# untitled2b.net
KiCad netlist of a schematic drawn in EAGLE
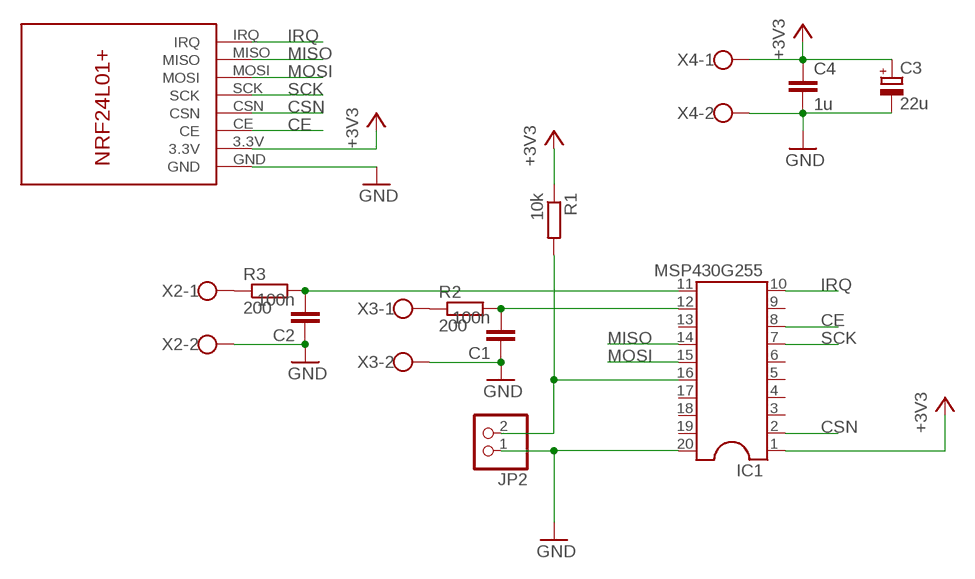
[diagram p0: schematic, sheet 1]

(export (version "E")
  (design (tool "Eeschema 10.0.6"))
  (components
    (comp (ref "C1")
      (value "100n")
      (footprint "eagle-import:C050-025X075")
      (libsource (lib "eagle-import") (part "C-EU050-025X075"))
    )
    (comp (ref "C2")
      (value "100n")
      (footprint "eagle-import:C050-025X075")
      (libsource (lib "eagle-import") (part "C-EU050-025X075"))
    )
    (comp (ref "C3")
      (value "22u")
      (footprint "eagle-import:E5-8,5")
      (libsource (lib "eagle-import") (part "CPOL-EUE5-8.5"))
    )
    (comp (ref "C4")
      (value "1u")
      (footprint "eagle-import:C050-045X075")
      (libsource (lib "eagle-import") (part "C-EU050-045X075"))
    )
    (comp (ref "IC1")
      (value "MSP430G255")
      (footprint "eagle-import:SOCKET-20")
      (libsource (lib "eagle-import") (part "DIL20S"))
    )
    (comp (ref "JP2")
      (value "PINHD-1X2")
      (footprint "eagle-import:1X02")
      (libsource (lib "eagle-import") (part "PINHD-1X2"))
    )
    (comp (ref "R1")
      (value "10k")
      (footprint "eagle-import:0207_10")
      (libsource (lib "eagle-import") (part "R-EU_0207/10"))
    )
    (comp (ref "R2")
      (value "200")
      (footprint "eagle-import:0207_10")
      (libsource (lib "eagle-import") (part "R-EU_0207/10"))
    )
    (comp (ref "R3")
      (value "200")
      (footprint "eagle-import:0207_10")
      (libsource (lib "eagle-import") (part "R-EU_0207/10"))
    )
    (comp (ref "U$1")
      (value "NRF24L01")
      (footprint "eagle-import:NRF24L01")
      (libsource (lib "eagle-import") (part "NRF24L01"))
    )
    (comp (ref "X2")
      (value "W237-102")
      (footprint "eagle-import:W237-102")
      (fields (field (name "MPN") "237-102"))
      (libsource (lib "eagle-import") (part "W237-102"))
    )
    (comp (ref "X3")
      (value "W237-102")
      (footprint "eagle-import:W237-102")
      (fields (field (name "MPN") "237-102"))
      (libsource (lib "eagle-import") (part "W237-102"))
    )
    (comp (ref "X4")
      (value "W237-102")
      (footprint "eagle-import:W237-102")
      (fields (field (name "MPN") "237-102"))
      (libsource (lib "eagle-import") (part "W237-102"))
    )
  )
  (nets
    (net (code "1") (name "+3V3") (class "Default")
      (node (ref "C3") (pin "+") (pinfunction "+_+") (pintype "passive"))
      (node (ref "C4") (pin "1") (pinfunction "1_1") (pintype "passive"))
      (node (ref "IC1") (pin "1") (pinfunction "1_1") (pintype "passive"))
      (node (ref "R1") (pin "1") (pinfunction "1_1") (pintype "passive"))
      (node (ref "U$1") (pin "3.3V") (pinfunction "3.3V_3.3V") (pintype "bidirectional"))
      (node (ref "X4") (pin "1") (pinfunction "KL_1") (pintype "passive"))
    )
    (net (code "2") (name "/CE") (class "Default")
      (node (ref "IC1") (pin "8") (pinfunction "8_8") (pintype "passive"))
      (node (ref "U$1") (pin "CE") (pinfunction "CE_CE") (pintype "bidirectional"))
    )
    (net (code "3") (name "/CSN") (class "Default")
      (node (ref "IC1") (pin "2") (pinfunction "2_2") (pintype "passive"))
      (node (ref "U$1") (pin "CSN") (pinfunction "CSN_CSN") (pintype "bidirectional"))
    )
    (net (code "4") (name "/IRQ") (class "Default")
      (node (ref "IC1") (pin "10") (pinfunction "10_10") (pintype "passive"))
      (node (ref "U$1") (pin "IRQ") (pinfunction "IRQ_IRQ") (pintype "bidirectional"))
    )
    (net (code "5") (name "/MISO") (class "Default")
      (node (ref "IC1") (pin "14") (pinfunction "14_14") (pintype "passive"))
      (node (ref "U$1") (pin "MISO") (pinfunction "MISO_MISO") (pintype "bidirectional"))
    )
    (net (code "6") (name "/MOSI") (class "Default")
      (node (ref "IC1") (pin "15") (pinfunction "15_15") (pintype "passive"))
      (node (ref "U$1") (pin "MOSI") (pinfunction "MOSI_MOSI") (pintype "bidirectional"))
    )
    (net (code "7") (name "/SCK") (class "Default")
      (node (ref "IC1") (pin "7") (pinfunction "7_7") (pintype "passive"))
      (node (ref "U$1") (pin "SCK") (pinfunction "SCK_SCK") (pintype "bidirectional"))
    )
    (net (code "8") (name "GND") (class "Default")
      (node (ref "C1") (pin "1") (pinfunction "1_1") (pintype "passive"))
      (node (ref "C2") (pin "1") (pinfunction "1_1") (pintype "passive"))
      (node (ref "C3") (pin "-") (pinfunction "-_-") (pintype "passive"))
      (node (ref "C4") (pin "2") (pinfunction "2_2") (pintype "passive"))
      (node (ref "IC1") (pin "20") (pinfunction "20_20") (pintype "passive"))
      (node (ref "JP2") (pin "1") (pinfunction "1_1") (pintype "passive"))
      (node (ref "U$1") (pin "GND") (pinfunction "GND_GND") (pintype "bidirectional"))
      (node (ref "X2") (pin "2") (pinfunction "KL_2") (pintype "passive"))
      (node (ref "X3") (pin "2") (pinfunction "KL_2") (pintype "passive"))
      (node (ref "X4") (pin "2") (pinfunction "KL_2") (pintype "passive"))
    )
    (net (code "9") (name "Net-(C1-Pad2)") (class "Default")
      (node (ref "C1") (pin "2") (pinfunction "2_2") (pintype "passive"))
      (node (ref "IC1") (pin "12") (pinfunction "12_12") (pintype "passive"))
      (node (ref "R2") (pin "2") (pinfunction "2_2") (pintype "passive"))
    )
    (net (code "10") (name "Net-(C2-Pad2)") (class "Default")
      (node (ref "C2") (pin "2") (pinfunction "2_2") (pintype "passive"))
      (node (ref "IC1") (pin "11") (pinfunction "11_11") (pintype "passive"))
      (node (ref "R3") (pin "2") (pinfunction "2_2") (pintype "passive"))
    )
    (net (code "11") (name "Net-(IC1-Pad16)") (class "Default")
      (node (ref "IC1") (pin "16") (pinfunction "16_16") (pintype "passive"))
      (node (ref "JP2") (pin "2") (pinfunction "2_2") (pintype "passive"))
      (node (ref "R1") (pin "2") (pinfunction "2_2") (pintype "passive"))
    )
    (net (code "12") (name "Net-(X2A-KL)") (class "Default")
      (node (ref "R3") (pin "1") (pinfunction "1_1") (pintype "passive"))
      (node (ref "X2") (pin "1") (pinfunction "KL_1") (pintype "passive"))
    )
    (net (code "13") (name "Net-(X3A-KL)") (class "Default")
      (node (ref "R2") (pin "1") (pinfunction "1_1") (pintype "passive"))
      (node (ref "X3") (pin "1") (pinfunction "KL_1") (pintype "passive"))
    )
    (net (code "14") (name "unconnected-(IC1-Pad3)") (class "Default")
      (node (ref "IC1") (pin "3") (pinfunction "3_3") (pintype "passive"))
    )
    (net (code "15") (name "unconnected-(IC1-Pad4)") (class "Default")
      (node (ref "IC1") (pin "4") (pinfunction "4_4") (pintype "passive"))
    )
    (net (code "16") (name "unconnected-(IC1-Pad5)") (class "Default")
      (node (ref "IC1") (pin "5") (pinfunction "5_5") (pintype "passive"))
    )
    (net (code "17") (name "unconnected-(IC1-Pad6)") (class "Default")
      (node (ref "IC1") (pin "6") (pinfunction "6_6") (pintype "passive"))
    )
    (net (code "18") (name "unconnected-(IC1-Pad9)") (class "Default")
      (node (ref "IC1") (pin "9") (pinfunction "9_9") (pintype "passive"))
    )
    (net (code "19") (name "unconnected-(IC1-Pad13)") (class "Default")
      (node (ref "IC1") (pin "13") (pinfunction "13_13") (pintype "passive"))
    )
    (net (code "20") (name "unconnected-(IC1-Pad17)") (class "Default")
      (node (ref "IC1") (pin "17") (pinfunction "17_17") (pintype "passive"))
    )
    (net (code "21") (name "unconnected-(IC1-Pad18)") (class "Default")
      (node (ref "IC1") (pin "18") (pinfunction "18_18") (pintype "passive"))
    )
    (net (code "22") (name "unconnected-(IC1-Pad19)") (class "Default")
      (node (ref "IC1") (pin "19") (pinfunction "19_19") (pintype "passive"))
    )
  )
)
